# adc.net
KiCad netlist of a schematic drawn in Altium Designer
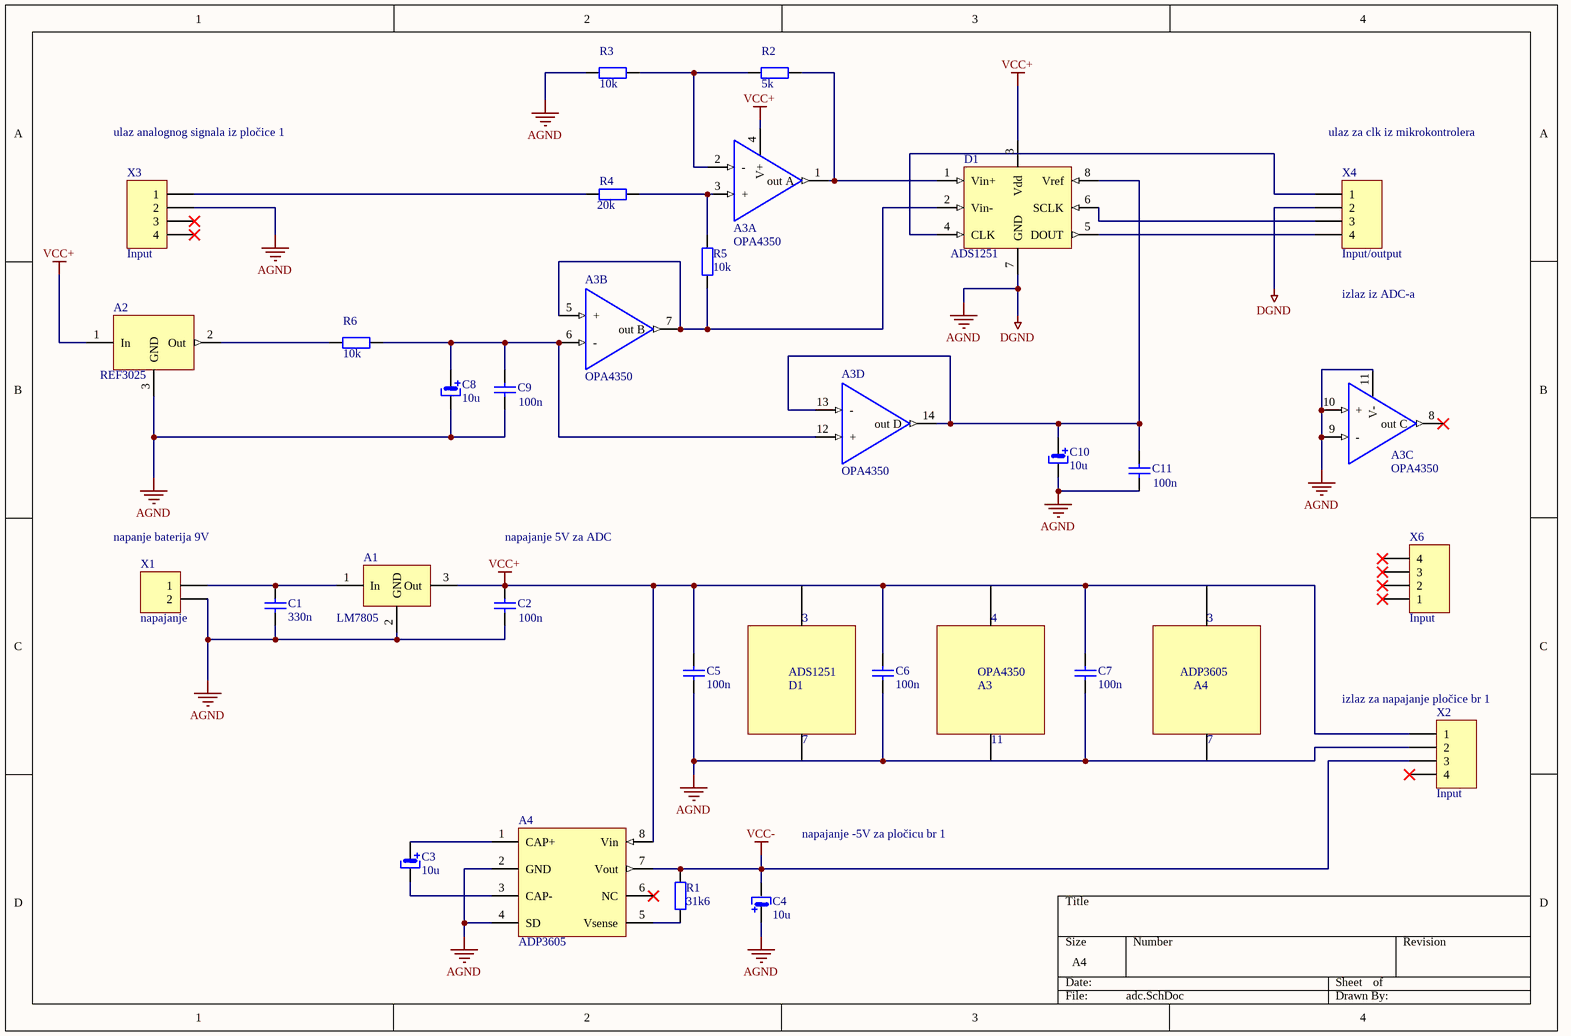
[diagram p0: adc.SchDoc]

(export (version "E")
  (design (tool "Eeschema 10.0.6"))
  (components
    (comp (ref "A1")
      (value "LM7805")
      (footprint "TO-220-AB")
      (libsource (lib "altium-import") (part "root_0_LM7805_"))
    )
    (comp (ref "A2")
      (value "REF3025")
      (footprint "SOT95P245X112-3N")
      (libsource (lib "altium-import") (part "root_2_mirrored_REF3040_"))
    )
    (comp (ref "A3")
      (value "OPA4350")
      (footprint "SOIC127P600X175-14N")
      (libsource (lib "altium-import") (part "root_3_OPA4350_"))
    )
    (comp (ref "A4")
      (value "ADP3605")
      (footprint "SO8_N")
      (libsource (lib "altium-import") (part "root_0_ADP3605_"))
    )
    (comp (ref "C1")
      (value "330n")
      (footprint "C0805")
      (description "Capacitor")
      (fields (field (name "PUBLISHER") "Altium Limited"))
      (libsource (lib "Miscellaneous Devices") (part "Cap"))
    )
    (comp (ref "C2")
      (value "100n")
      (footprint "C0805")
      (description "Capacitor")
      (fields (field (name "PUBLISHER") "Altium Limited"))
      (libsource (lib "Miscellaneous Devices") (part "Cap"))
    )
    (comp (ref "C3")
      (value "10u")
      (footprint "C0805")
      (libsource (lib "altium-import") (part "root_0_elko2_"))
    )
    (comp (ref "C4")
      (value "10u")
      (footprint "C0805")
      (libsource (lib "altium-import") (part "root_2_elko2_"))
    )
    (comp (ref "C5")
      (value "100n")
      (footprint "C0805")
      (description "Capacitor")
      (fields (field (name "PUBLISHER") "Altium Limited"))
      (libsource (lib "Miscellaneous Devices") (part "Cap"))
    )
    (comp (ref "C6")
      (value "100n")
      (footprint "C0805")
      (description "Capacitor")
      (fields (field (name "PUBLISHER") "Altium Limited"))
      (libsource (lib "Miscellaneous Devices") (part "Cap"))
    )
    (comp (ref "C7")
      (value "100n")
      (footprint "C0805")
      (description "Capacitor")
      (fields (field (name "PUBLISHER") "Altium Limited"))
      (libsource (lib "Miscellaneous Devices") (part "Cap"))
    )
    (comp (ref "C8")
      (value "10u")
      (footprint "C0805")
      (libsource (lib "altium-import") (part "root_0_elko2_"))
    )
    (comp (ref "C9")
      (value "100n")
      (footprint "C0805")
      (description "Capacitor")
      (fields (field (name "PUBLISHER") "Altium Limited"))
      (libsource (lib "Miscellaneous Devices") (part "Cap"))
    )
    (comp (ref "C10")
      (value "10u")
      (footprint "C0805")
      (libsource (lib "altium-import") (part "root_0_elko2_"))
    )
    (comp (ref "C11")
      (value "100n")
      (footprint "C0805")
      (description "Capacitor")
      (fields (field (name "PUBLISHER") "Altium Limited"))
      (libsource (lib "Miscellaneous Devices") (part "Cap"))
    )
    (comp (ref "D1")
      (value "ADS1251")
      (footprint "SOIC127P600X175-8N")
      (libsource (lib "altium-import") (part "root_0_ADS1251_"))
    )
    (comp (ref "R1")
      (value "31k6")
      (footprint "C0805")
      (description "Resistor")
      (fields (field (name "PUBLISHER") "Altium Limited"))
      (libsource (lib "Miscellaneous Devices") (part "Res2"))
    )
    (comp (ref "R2")
      (value "5k")
      (footprint "C0805")
      (description "Resistor")
      (fields (field (name "PUBLISHER") "Altium Limited"))
      (libsource (lib "") (part "Res2_1"))
    )
    (comp (ref "R3")
      (value "10k")
      (footprint "C0805")
      (description "Resistor")
      (fields (field (name "PUBLISHER") "Altium Limited"))
      (libsource (lib "") (part "Res2_1"))
    )
    (comp (ref "R4")
      (value "20k")
      (footprint "C0805")
      (description "Resistor")
      (fields (field (name "PUBLISHER") "Altium Limited"))
      (libsource (lib "") (part "Res2_1"))
    )
    (comp (ref "R5")
      (value "10k")
      (footprint "C0805")
      (description "Resistor")
      (fields (field (name "PUBLISHER") "Altium Limited"))
      (libsource (lib "") (part "Res2_2"))
    )
    (comp (ref "R6")
      (value "10k")
      (footprint "C0805")
      (description "Resistor")
      (fields (field (name "PUBLISHER") "Altium Limited"))
      (libsource (lib "") (part "Res2_1"))
    )
    (comp (ref "X1")
      (value "napajanje")
      (footprint "HDR1X2")
      (description "Header, 2-Pin, Right Angle")
      (fields (field (name "PUBLISHER") "Altium Limited"))
      (libsource (lib "Miscellaneous Connectors") (part "Header 2H"))
    )
    (comp (ref "X2")
      (value "Input")
      (footprint "HDR1X4")
      (description "Header, 4-Pin, Right Angle")
      (fields (field (name "PUBLISHER") "Altium Limited"))
      (libsource (lib "") (part "Header 4H_1"))
    )
    (comp (ref "X3")
      (value "Input")
      (footprint "HDR1X4")
      (description "Header, 4-Pin, Right Angle")
      (fields (field (name "PUBLISHER") "Altium Limited"))
      (libsource (lib "") (part "Header 4H_2"))
    )
    (comp (ref "X4")
      (value "Input/output")
      (footprint "HDR1X4")
      (description "Header, 4-Pin, Right Angle")
      (fields (field (name "PUBLISHER") "Altium Limited"))
      (libsource (lib "") (part "Header 4H_1"))
    )
    (comp (ref "X6")
      (value "Input")
      (footprint "HDR1X4")
      (description "Header, 4-Pin, Right Angle")
      (fields (field (name "PUBLISHER") "Altium Limited"))
      (libsource (lib "Miscellaneous Connectors") (part "Header 4H"))
    )
  )
  (nets
    (net (code "1") (name "AGND") (class "Default")
      (node (ref "A1") (pin "2") (pinfunction "GND_2") (pintype "power_in"))
      (node (ref "A2") (pin "3") (pinfunction "GND_3") (pintype "passive"))
      (node (ref "A3") (pin "10") (pinfunction "+_10") (pintype "input"))
      (node (ref "A3") (pin "11") (pinfunction "V-_11") (pintype "power_in"))
      (node (ref "A3") (pin "9") (pinfunction "-_9") (pintype "input"))
      (node (ref "A4") (pin "2") (pinfunction "GND_2") (pintype "power_in"))
      (node (ref "A4") (pin "4") (pinfunction "SD_4") (pintype "passive"))
      (node (ref "C1") (pin "1") (pinfunction "1_1") (pintype "passive"))
      (node (ref "C10") (pin "2") (pinfunction "2_2") (pintype "passive"))
      (node (ref "C11") (pin "1") (pinfunction "1_1") (pintype "passive"))
      (node (ref "C2") (pin "1") (pinfunction "1_1") (pintype "passive"))
      (node (ref "C4") (pin "1") (pinfunction "1_1") (pintype "passive"))
      (node (ref "C5") (pin "1") (pinfunction "1_1") (pintype "passive"))
      (node (ref "C6") (pin "1") (pinfunction "1_1") (pintype "passive"))
      (node (ref "C7") (pin "1") (pinfunction "1_1") (pintype "passive"))
      (node (ref "C8") (pin "2") (pinfunction "2_2") (pintype "passive"))
      (node (ref "C9") (pin "1") (pinfunction "1_1") (pintype "passive"))
      (node (ref "D1") (pin "7") (pinfunction "GND_7") (pintype "power_in"))
      (node (ref "R3") (pin "2") (pinfunction "2_2") (pintype "passive"))
      (node (ref "X1") (pin "2") (pinfunction "2_2") (pintype "passive"))
      (node (ref "X2") (pin "2") (pinfunction "2_2") (pintype "passive"))
      (node (ref "X3") (pin "2") (pinfunction "2_2") (pintype "passive"))
      (node (ref "X4") (pin "2") (pinfunction "2_2") (pintype "passive"))
    )
    (net (code "2") (name "Net-(A1-In)") (class "Default")
      (node (ref "A1") (pin "1") (pinfunction "In_1") (pintype "power_in"))
      (node (ref "C1") (pin "2") (pinfunction "2_2") (pintype "passive"))
      (node (ref "X1") (pin "1") (pinfunction "1_1") (pintype "passive"))
    )
    (net (code "3") (name "Net-(A2-Out)") (class "Default")
      (node (ref "A2") (pin "2") (pinfunction "Out_2") (pintype "output"))
      (node (ref "R6") (pin "2") (pinfunction "2_2") (pintype "passive"))
    )
    (net (code "4") (name "Net-(A3A-+)") (class "Default")
      (node (ref "A3") (pin "3") (pinfunction "+_3") (pintype "input"))
      (node (ref "R4") (pin "1") (pinfunction "1_1") (pintype "passive"))
      (node (ref "R5") (pin "1") (pinfunction "1_1") (pintype "passive"))
    )
    (net (code "5") (name "Net-(A3A--)") (class "Default")
      (node (ref "A3") (pin "2") (pinfunction "-_2") (pintype "input"))
      (node (ref "R2") (pin "2") (pinfunction "2_2") (pintype "passive"))
      (node (ref "R3") (pin "1") (pinfunction "1_1") (pintype "passive"))
    )
    (net (code "6") (name "Net-(A3A-out_A)") (class "Default")
      (node (ref "A3") (pin "1") (pinfunction "out_A_1") (pintype "output"))
      (node (ref "D1") (pin "1") (pinfunction "Vin+_1") (pintype "input"))
      (node (ref "R2") (pin "1") (pinfunction "1_1") (pintype "passive"))
    )
    (net (code "7") (name "Net-(A3B-+)") (class "Default")
      (node (ref "A3") (pin "5") (pinfunction "+_5") (pintype "input"))
      (node (ref "A3") (pin "7") (pinfunction "out_B_7") (pintype "output"))
      (node (ref "D1") (pin "2") (pinfunction "Vin-_2") (pintype "input"))
      (node (ref "R5") (pin "2") (pinfunction "2_2") (pintype "passive"))
    )
    (net (code "8") (name "Net-(A3B--)") (class "Default")
      (node (ref "A3") (pin "12") (pinfunction "+_12") (pintype "input"))
      (node (ref "A3") (pin "6") (pinfunction "-_6") (pintype "input"))
      (node (ref "C8") (pin "1") (pinfunction "1_1") (pintype "passive"))
      (node (ref "C9") (pin "2") (pinfunction "2_2") (pintype "passive"))
      (node (ref "R6") (pin "1") (pinfunction "1_1") (pintype "passive"))
    )
    (net (code "9") (name "Net-(A3D--)") (class "Default")
      (node (ref "A3") (pin "13") (pinfunction "-_13") (pintype "input"))
      (node (ref "A3") (pin "14") (pinfunction "out_D_14") (pintype "output"))
      (node (ref "C10") (pin "1") (pinfunction "1_1") (pintype "passive"))
      (node (ref "C11") (pin "2") (pinfunction "2_2") (pintype "passive"))
      (node (ref "D1") (pin "8") (pinfunction "Vref_8") (pintype "input"))
    )
    (net (code "10") (name "Net-(A4-CAP+)") (class "Default")
      (node (ref "A4") (pin "1") (pinfunction "CAP+_1") (pintype "passive"))
      (node (ref "C3") (pin "1") (pinfunction "1_1") (pintype "passive"))
    )
    (net (code "11") (name "Net-(A4-CAP-)") (class "Default")
      (node (ref "A4") (pin "3") (pinfunction "CAP-_3") (pintype "passive"))
      (node (ref "C3") (pin "2") (pinfunction "2_2") (pintype "passive"))
    )
    (net (code "12") (name "Net-(A4-Vsense)") (class "Default")
      (node (ref "A4") (pin "5") (pinfunction "Vsense_5") (pintype "passive"))
      (node (ref "R1") (pin "1") (pinfunction "1_1") (pintype "passive"))
    )
    (net (code "13") (name "Net-(D1-CLK)") (class "Default")
      (node (ref "D1") (pin "4") (pinfunction "CLK_4") (pintype "input"))
      (node (ref "X4") (pin "1") (pinfunction "1_1") (pintype "passive"))
    )
    (net (code "14") (name "Net-(D1-DOUT)") (class "Default")
      (node (ref "D1") (pin "5") (pinfunction "DOUT_5") (pintype "output"))
      (node (ref "X4") (pin "4") (pinfunction "4_4") (pintype "passive"))
    )
    (net (code "15") (name "Net-(D1-SCLK)") (class "Default")
      (node (ref "D1") (pin "6") (pinfunction "SCLK_6") (pintype "input"))
      (node (ref "X4") (pin "3") (pinfunction "3_3") (pintype "passive"))
    )
    (net (code "16") (name "Net-(R4-Pad2)") (class "Default")
      (node (ref "R4") (pin "2") (pinfunction "2_2") (pintype "passive"))
      (node (ref "X3") (pin "1") (pinfunction "1_1") (pintype "passive"))
    )
    (net (code "17") (name "VCC+") (class "Default")
      (node (ref "A1") (pin "3") (pinfunction "Out_3") (pintype "power_in"))
      (node (ref "A2") (pin "1") (pinfunction "In_1") (pintype "power_in"))
      (node (ref "A3") (pin "4") (pinfunction "V+_4") (pintype "power_in"))
      (node (ref "A4") (pin "8") (pinfunction "Vin_8") (pintype "input"))
      (node (ref "C2") (pin "2") (pinfunction "2_2") (pintype "passive"))
      (node (ref "C5") (pin "2") (pinfunction "2_2") (pintype "passive"))
      (node (ref "C6") (pin "2") (pinfunction "2_2") (pintype "passive"))
      (node (ref "C7") (pin "2") (pinfunction "2_2") (pintype "passive"))
      (node (ref "D1") (pin "3") (pinfunction "Vdd_3") (pintype "power_in"))
      (node (ref "X2") (pin "1") (pinfunction "1_1") (pintype "passive"))
    )
    (net (code "18") (name "VCC-") (class "Default")
      (node (ref "A4") (pin "7") (pinfunction "Vout_7") (pintype "output"))
      (node (ref "C4") (pin "2") (pinfunction "2_2") (pintype "passive"))
      (node (ref "R1") (pin "2") (pinfunction "2_2") (pintype "passive"))
      (node (ref "X2") (pin "3") (pinfunction "3_3") (pintype "passive"))
    )
    (net (code "19") (name "unconnected-(A3C-out_C-Pad8)") (class "Default")
      (node (ref "A3") (pin "8") (pinfunction "out_C_8") (pintype "output+no_connect"))
    )
    (net (code "20") (name "unconnected-(A4-NC-Pad6)") (class "Default")
      (node (ref "A4") (pin "6") (pinfunction "NC_6") (pintype "passive+no_connect"))
    )
    (net (code "21") (name "unconnected-(X2-Pad4)") (class "Default")
      (node (ref "X2") (pin "4") (pinfunction "4_4") (pintype "passive+no_connect"))
    )
    (net (code "22") (name "unconnected-(X3-Pad3)") (class "Default")
      (node (ref "X3") (pin "3") (pinfunction "3_3") (pintype "passive+no_connect"))
    )
    (net (code "23") (name "unconnected-(X3-Pad4)") (class "Default")
      (node (ref "X3") (pin "4") (pinfunction "4_4") (pintype "passive+no_connect"))
    )
    (net (code "24") (name "unconnected-(X6-Pad1)") (class "Default")
      (node (ref "X6") (pin "1") (pinfunction "1_1") (pintype "passive+no_connect"))
    )
    (net (code "25") (name "unconnected-(X6-Pad2)") (class "Default")
      (node (ref "X6") (pin "2") (pinfunction "2_2") (pintype "passive+no_connect"))
    )
    (net (code "26") (name "unconnected-(X6-Pad3)") (class "Default")
      (node (ref "X6") (pin "3") (pinfunction "3_3") (pintype "passive+no_connect"))
    )
    (net (code "27") (name "unconnected-(X6-Pad4)") (class "Default")
      (node (ref "X6") (pin "4") (pinfunction "4_4") (pintype "passive+no_connect"))
    )
  )
)
